# gate.net
KiCad netlist of a schematic drawn in EAGLE
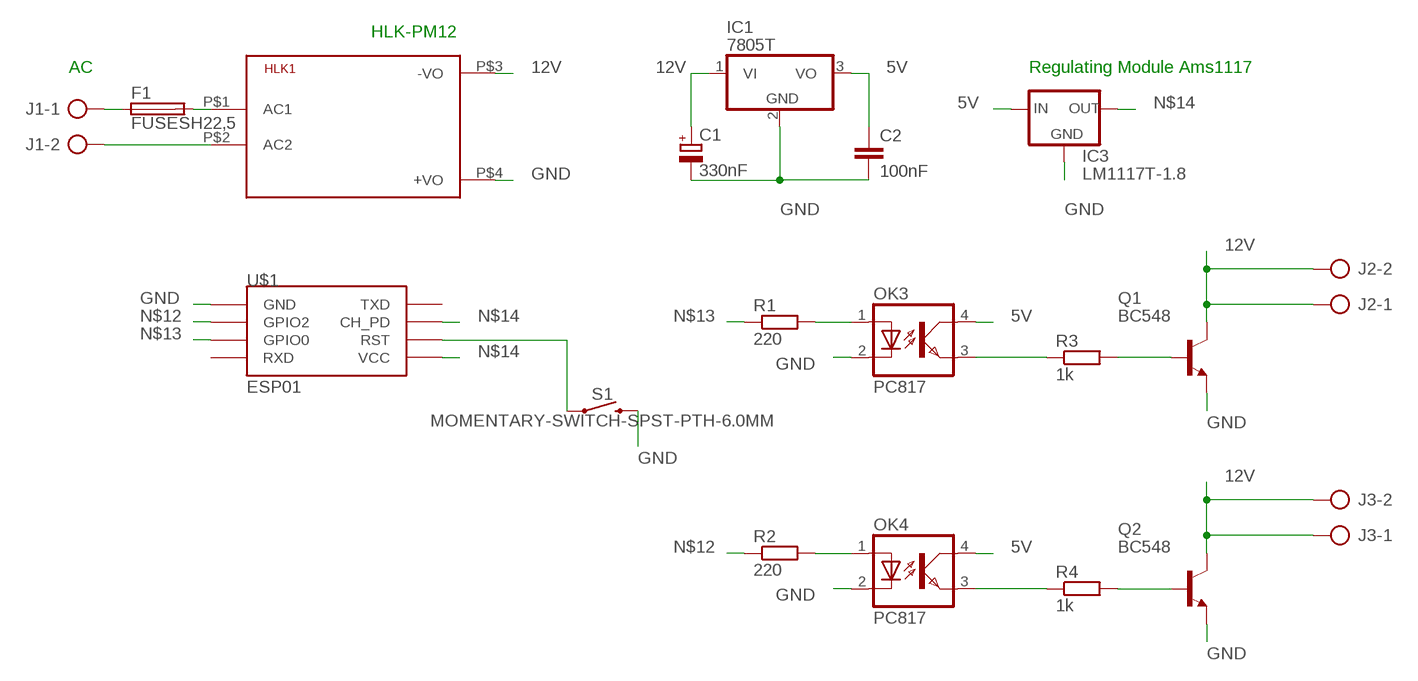
[diagram p0: schematic, sheet 1]

(export (version "E")
  (design (tool "Eeschema 10.0.6"))
  (components
    (comp (ref "C1")
      (value "330nF")
      (footprint "eagle-import:E2,5-6")
      (libsource (lib "eagle-import") (part "CPOL-EUE2.5-6"))
    )
    (comp (ref "C2")
      (value "100nF")
      (footprint "eagle-import:C050-024X044")
      (libsource (lib "eagle-import") (part "C-EU050-024X044"))
    )
    (comp (ref "F1")
      (value "FUSESH22,5")
      (footprint "eagle-import:SH22,5")
      (libsource (lib "eagle-import") (part "FUSESH22,5"))
    )
    (comp (ref "HLK1")
      (value "HLK-PM013W")
      (footprint "eagle-import:HLK-PM01")
      (libsource (lib "eagle-import") (part "HLK-PM013W"))
    )
    (comp (ref "IC1")
      (value "7805T")
      (footprint "eagle-import:TO220H")
      (libsource (lib "eagle-import") (part "78T05"))
    )
    (comp (ref "IC3")
      (value "LM1117T-1.8")
      (footprint "eagle-import:TO220")
      (libsource (lib "eagle-import") (part "LM1117T-1.8"))
    )
    (comp (ref "J1")
      (value "AK500/2-H")
      (footprint "eagle-import:AK500_2-H")
      (libsource (lib "eagle-import") (part "AK500/2-H"))
    )
    (comp (ref "J2")
      (value "AK500/2-H")
      (footprint "eagle-import:AK500_2-H")
      (libsource (lib "eagle-import") (part "AK500/2-H"))
    )
    (comp (ref "J3")
      (value "AK500/2-H")
      (footprint "eagle-import:AK500_2-H")
      (libsource (lib "eagle-import") (part "AK500/2-H"))
    )
    (comp (ref "OK3")
      (value "PC817")
      (footprint "eagle-import:DIL04")
      (fields (field (name "MPN") "PC817X4J000F"))
      (libsource (lib "eagle-import") (part "PC817"))
    )
    (comp (ref "OK4")
      (value "PC817")
      (footprint "eagle-import:DIL04")
      (fields (field (name "MPN") "PC817X4J000F"))
      (libsource (lib "eagle-import") (part "PC817"))
    )
    (comp (ref "Q1")
      (value "BC548")
      (footprint "eagle-import:TO92-EBC")
      (libsource (lib "eagle-import") (part "BC548"))
    )
    (comp (ref "Q2")
      (value "BC548")
      (footprint "eagle-import:TO92-EBC")
      (libsource (lib "eagle-import") (part "BC548"))
    )
    (comp (ref "R1")
      (value "220")
      (footprint "eagle-import:0204_7")
      (libsource (lib "eagle-import") (part "R-EU_0204/7"))
    )
    (comp (ref "R2")
      (value "220")
      (footprint "eagle-import:0204_7")
      (libsource (lib "eagle-import") (part "R-EU_0204/7"))
    )
    (comp (ref "R3")
      (value "1k")
      (footprint "eagle-import:0204_7")
      (libsource (lib "eagle-import") (part "R-EU_0204/7"))
    )
    (comp (ref "R4")
      (value "1k")
      (footprint "eagle-import:0204_7")
      (libsource (lib "eagle-import") (part "R-EU_0204/7"))
    )
    (comp (ref "S1")
      (value "MOMENTARY-SWITCH-SPST-PTH-6.0MM")
      (footprint "eagle-import:TACTILE_SWITCH_PTH_6.0MM")
      (libsource (lib "eagle-import") (part "MOMENTARY-SWITCH-SPST-PTH-6.0MM"))
    )
    (comp (ref "U$1")
      (value "ESP01")
      (footprint "eagle-import:ESP01")
      (libsource (lib "eagle-import") (part "ESP01"))
    )
  )
  (nets
    (net (code "1") (name "/5V") (class "Default")
      (node (ref "C2") (pin "1") (pinfunction "1_1") (pintype "passive"))
      (node (ref "IC1") (pin "3") (pinfunction "VO_3") (pintype "passive"))
      (node (ref "IC3") (pin "3") (pinfunction "IN_3") (pintype "input"))
      (node (ref "OK3") (pin "4") (pinfunction "COL_4") (pintype "passive"))
      (node (ref "OK4") (pin "4") (pinfunction "COL_4") (pintype "passive"))
    )
    (net (code "2") (name "/12V") (class "Default")
      (node (ref "C1") (pin "+") (pinfunction "+_+") (pintype "passive"))
      (node (ref "HLK1") (pin "P$3") (pinfunction "-VO_P$3") (pintype "bidirectional"))
      (node (ref "IC1") (pin "1") (pinfunction "VI_1") (pintype "input"))
      (node (ref "J2") (pin "1") (pinfunction "KL_1") (pintype "passive"))
      (node (ref "J2") (pin "2") (pinfunction "KL_2") (pintype "passive"))
      (node (ref "J3") (pin "1") (pinfunction "KL_1") (pintype "passive"))
      (node (ref "J3") (pin "2") (pinfunction "KL_2") (pintype "passive"))
      (node (ref "Q1") (pin "C") (pinfunction "C_C") (pintype "passive"))
      (node (ref "Q2") (pin "C") (pinfunction "C_C") (pintype "passive"))
    )
    (net (code "3") (name "/GND") (class "Default")
      (node (ref "C1") (pin "-") (pinfunction "-_-") (pintype "passive"))
      (node (ref "C2") (pin "2") (pinfunction "2_2") (pintype "passive"))
      (node (ref "HLK1") (pin "P$4") (pinfunction "+VO_P$4") (pintype "bidirectional"))
      (node (ref "IC1") (pin "2") (pinfunction "GND_2") (pintype "passive"))
      (node (ref "IC3") (pin "1") (pinfunction "GND_1") (pintype "input"))
      (node (ref "OK3") (pin "2") (pinfunction "C_2") (pintype "passive"))
      (node (ref "OK4") (pin "2") (pinfunction "C_2") (pintype "passive"))
      (node (ref "Q1") (pin "E") (pinfunction "E_E") (pintype "passive"))
      (node (ref "Q2") (pin "E") (pinfunction "E_E") (pintype "passive"))
      (node (ref "S1") (pin "3") (pinfunction "2_3") (pintype "passive"))
      (node (ref "U$1") (pin "GND") (pinfunction "GND_GND") (pintype "bidirectional"))
    )
    (net (code "4") (name "/N$12") (class "Default")
      (node (ref "R2") (pin "1") (pinfunction "1_1") (pintype "passive"))
      (node (ref "U$1") (pin "GPIO2") (pinfunction "GPIO2_GPIO2") (pintype "bidirectional"))
    )
    (net (code "5") (name "/N$13") (class "Default")
      (node (ref "R1") (pin "1") (pinfunction "1_1") (pintype "passive"))
      (node (ref "U$1") (pin "GPIO0") (pinfunction "GPIO0_GPIO0") (pintype "bidirectional"))
    )
    (net (code "6") (name "/N$14") (class "Default")
      (node (ref "IC3") (pin "2") (pinfunction "OUT_2") (pintype "passive"))
      (node (ref "U$1") (pin "CH_PD") (pinfunction "CH_PD_CH_PD") (pintype "bidirectional"))
      (node (ref "U$1") (pin "VCC") (pinfunction "VCC_VCC") (pintype "bidirectional"))
    )
    (net (code "7") (name "Net-(HLK1-AC1)") (class "Default")
      (node (ref "F1") (pin "2") (pinfunction "2_2") (pintype "passive"))
      (node (ref "HLK1") (pin "P$1") (pinfunction "AC1_P$1") (pintype "bidirectional"))
    )
    (net (code "8") (name "Net-(HLK1-AC2)") (class "Default")
      (node (ref "HLK1") (pin "P$2") (pinfunction "AC2_P$2") (pintype "bidirectional"))
      (node (ref "J1") (pin "2") (pinfunction "KL_2") (pintype "passive"))
    )
    (net (code "9") (name "Net-(J1A-KL)") (class "Default")
      (node (ref "F1") (pin "1") (pinfunction "1_1") (pintype "passive"))
      (node (ref "J1") (pin "1") (pinfunction "KL_1") (pintype "passive"))
    )
    (net (code "10") (name "Net-(OK3-A)") (class "Default")
      (node (ref "OK3") (pin "1") (pinfunction "A_1") (pintype "passive"))
      (node (ref "R1") (pin "2") (pinfunction "2_2") (pintype "passive"))
    )
    (net (code "11") (name "Net-(OK3-EMIT)") (class "Default")
      (node (ref "OK3") (pin "3") (pinfunction "EMIT_3") (pintype "passive"))
      (node (ref "R3") (pin "1") (pinfunction "1_1") (pintype "passive"))
    )
    (net (code "12") (name "Net-(OK4-A)") (class "Default")
      (node (ref "OK4") (pin "1") (pinfunction "A_1") (pintype "passive"))
      (node (ref "R2") (pin "2") (pinfunction "2_2") (pintype "passive"))
    )
    (net (code "13") (name "Net-(OK4-EMIT)") (class "Default")
      (node (ref "OK4") (pin "3") (pinfunction "EMIT_3") (pintype "passive"))
      (node (ref "R4") (pin "1") (pinfunction "1_1") (pintype "passive"))
    )
    (net (code "14") (name "Net-(Q1-PadB)") (class "Default")
      (node (ref "Q1") (pin "B") (pinfunction "B_B") (pintype "passive"))
      (node (ref "R3") (pin "2") (pinfunction "2_2") (pintype "passive"))
    )
    (net (code "15") (name "Net-(Q2-PadB)") (class "Default")
      (node (ref "Q2") (pin "B") (pinfunction "B_B") (pintype "passive"))
      (node (ref "R4") (pin "2") (pinfunction "2_2") (pintype "passive"))
    )
    (net (code "16") (name "Net-(S1-Pad1)") (class "Default")
      (node (ref "S1") (pin "1") (pinfunction "1_1") (pintype "passive"))
      (node (ref "U$1") (pin "RST") (pinfunction "RST_RST") (pintype "bidirectional"))
    )
    (net (code "17") (name "unconnected-(U$1-RXD-PadRX)") (class "Default")
      (node (ref "U$1") (pin "RX") (pinfunction "RXD_RX") (pintype "bidirectional"))
    )
    (net (code "18") (name "unconnected-(U$1-TXD-PadTX)") (class "Default")
      (node (ref "U$1") (pin "TX") (pinfunction "TXD_TX") (pintype "bidirectional"))
    )
  )
)
